# ncat.net
KiCad netlist of a schematic drawn in EAGLE
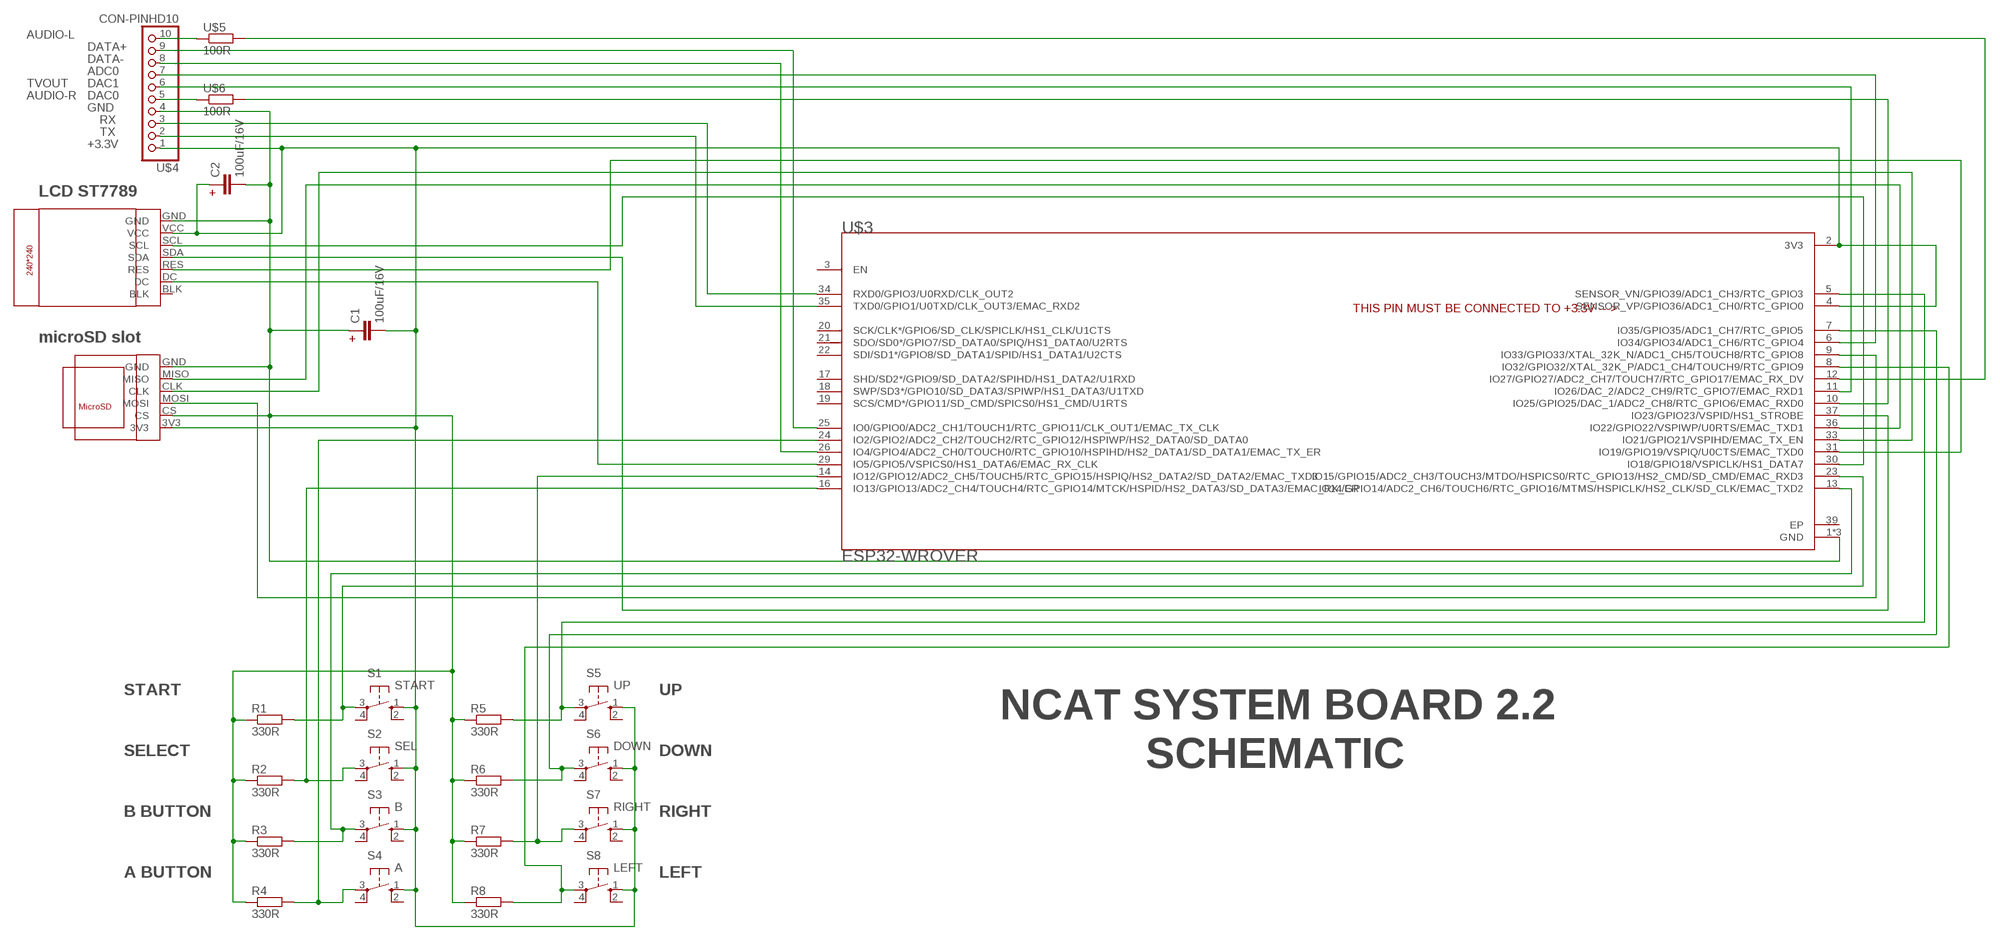
[diagram p0: schematic, sheet 1]

(export (version "E")
  (design (tool "Eeschema 10.0.6"))
  (components
    (comp (ref "C1")
      (value "100uF/16V")
      (footprint "eagle-import:C1210")
      (libsource (lib "eagle-import") (part "C-EUC1210"))
    )
    (comp (ref "C2")
      (value "100uF/16V")
      (footprint "eagle-import:C1210")
      (libsource (lib "eagle-import") (part "C-EUC1210"))
    )
    (comp (ref "R1")
      (value "330R")
      (footprint "eagle-import:R0204_5H")
      (libsource (lib "eagle-import") (part "RESISTORR204/5H"))
    )
    (comp (ref "R2")
      (value "330R")
      (footprint "eagle-import:R0204_5H")
      (libsource (lib "eagle-import") (part "RESISTORR204/5H"))
    )
    (comp (ref "R3")
      (value "330R")
      (footprint "eagle-import:R0204_5H")
      (libsource (lib "eagle-import") (part "RESISTORR204/5H"))
    )
    (comp (ref "R4")
      (value "330R")
      (footprint "eagle-import:R0204_5H")
      (libsource (lib "eagle-import") (part "RESISTORR204/5H"))
    )
    (comp (ref "R5")
      (value "330R")
      (footprint "eagle-import:R0204_5H")
      (libsource (lib "eagle-import") (part "RESISTORR204/5H"))
    )
    (comp (ref "R6")
      (value "330R")
      (footprint "eagle-import:R0204_5H")
      (libsource (lib "eagle-import") (part "RESISTORR204/5H"))
    )
    (comp (ref "R7")
      (value "330R")
      (footprint "eagle-import:R0204_5H")
      (libsource (lib "eagle-import") (part "RESISTORR204/5H"))
    )
    (comp (ref "R8")
      (value "330R")
      (footprint "eagle-import:R0204_5H")
      (libsource (lib "eagle-import") (part "RESISTORR204/5H"))
    )
    (comp (ref "S1")
      (value "START")
      (footprint "eagle-import:B3F-10XX")
      (fields (field (name "MPN") "B3F-1000"))
      (libsource (lib "eagle-import") (part "10-XX"))
    )
    (comp (ref "S2")
      (value "SEL")
      (footprint "eagle-import:B3F-10XX")
      (fields (field (name "MPN") "B3F-1000"))
      (libsource (lib "eagle-import") (part "10-XX"))
    )
    (comp (ref "S3")
      (value "B")
      (footprint "eagle-import:B3F-10XX")
      (fields (field (name "MPN") "B3F-1000"))
      (libsource (lib "eagle-import") (part "10-XX"))
    )
    (comp (ref "S4")
      (value "A")
      (footprint "eagle-import:B3F-10XX")
      (fields (field (name "MPN") "B3F-1000"))
      (libsource (lib "eagle-import") (part "10-XX"))
    )
    (comp (ref "S5")
      (value "UP")
      (footprint "eagle-import:B3F-10XX")
      (fields (field (name "MPN") "B3F-1000"))
      (libsource (lib "eagle-import") (part "10-XX"))
    )
    (comp (ref "S6")
      (value "DOWN")
      (footprint "eagle-import:B3F-10XX")
      (fields (field (name "MPN") "B3F-1000"))
      (libsource (lib "eagle-import") (part "10-XX"))
    )
    (comp (ref "S7")
      (value "RIGHT")
      (footprint "eagle-import:B3F-10XX")
      (fields (field (name "MPN") "B3F-1000"))
      (libsource (lib "eagle-import") (part "10-XX"))
    )
    (comp (ref "S8")
      (value "LEFT")
      (footprint "eagle-import:B3F-10XX")
      (fields (field (name "MPN") "B3F-1000"))
      (libsource (lib "eagle-import") (part "10-XX"))
    )
    (comp (ref "U$1")
      (value "MICROSD-CARD-MODULESMD")
      (footprint "eagle-import:MICROSD-CARD-MODULE-SMD")
      (libsource (lib "eagle-import") (part "MICROSD-CARD-MODULESMD"))
    )
    (comp (ref "U$3")
      (value "ESP32-WROVER")
      (footprint "eagle-import:XCVR-ESP32-WROVER")
      (libsource (lib "eagle-import") (part "ESP32-WROVER"))
    )
    (comp (ref "U$4")
      (value "CON-PINHD10")
      (footprint "eagle-import:PIN1X10")
      (libsource (lib "eagle-import") (part "CON-PINHD10"))
    )
    (comp (ref "U$5")
      (value "100R")
      (footprint "eagle-import:R1206_SMD")
      (libsource (lib "eagle-import") (part "RESISTORR1206/SMD"))
    )
    (comp (ref "U$6")
      (value "100R")
      (footprint "eagle-import:R1206_SMD")
      (libsource (lib "eagle-import") (part "RESISTORR1206/SMD"))
    )
    (comp (ref "U$7")
      (value "LCD-ST7789-1.3INCH")
      (footprint "eagle-import:LCD-ST7789-1.3INCH")
      (libsource (lib "eagle-import") (part "LCD-ST7789-1.3INCH"))
    )
  )
  (nets
    (net (code "1") (name "/EP") (class "Default")
      (node (ref "U$3") (pin "39") (pinfunction "EP_39") (pintype "power_in"))
    )
    (net (code "2") (name "Net-(C1-Pad1)") (class "Default")
      (node (ref "C1") (pin "1") (pinfunction "1_1") (pintype "passive"))
      (node (ref "C2") (pin "2") (pinfunction "2_2") (pintype "passive"))
      (node (ref "R1") (pin "1") (pinfunction "1_1") (pintype "passive"))
      (node (ref "R2") (pin "1") (pinfunction "1_1") (pintype "passive"))
      (node (ref "R3") (pin "1") (pinfunction "1_1") (pintype "passive"))
      (node (ref "R4") (pin "1") (pinfunction "1_1") (pintype "passive"))
      (node (ref "R5") (pin "1") (pinfunction "1_1") (pintype "passive"))
      (node (ref "R6") (pin "1") (pinfunction "1_1") (pintype "passive"))
      (node (ref "R7") (pin "1") (pinfunction "1_1") (pintype "passive"))
      (node (ref "R8") (pin "1") (pinfunction "1_1") (pintype "passive"))
      (node (ref "U$1") (pin "CS") (pinfunction "CS_CS") (pintype "bidirectional"))
      (node (ref "U$1") (pin "GND") (pinfunction "GND_GND") (pintype "bidirectional"))
      (node (ref "U$3") (pin "1") (pinfunction "GND_1") (pintype "power_in"))
      (node (ref "U$3") (pin "15") (pinfunction "GND_15") (pintype "power_in"))
      (node (ref "U$3") (pin "38") (pinfunction "GND_38") (pintype "power_in"))
      (node (ref "U$4") (pin "4") (pinfunction "4_4") (pintype "passive"))
      (node (ref "U$7") (pin "GND") (pinfunction "GND_GND") (pintype "bidirectional"))
    )
    (net (code "3") (name "Net-(S1-P)") (class "Default")
      (node (ref "R1") (pin "2") (pinfunction "2_2") (pintype "passive"))
      (node (ref "S1") (pin "3") (pinfunction "P_3") (pintype "passive"))
      (node (ref "U$3") (pin "23") (pinfunction "IO15/GPIO15/ADC2_CH3/TOUCH3/MTDO/HSPICS0/RTC_GPIO13/HS2_CMD/SD_CMD/EMAC_RXD3_23") (pintype "bidirectional"))
    )
    (net (code "4") (name "Net-(S1-S)") (class "Default")
      (node (ref "C1") (pin "2") (pinfunction "2_2") (pintype "passive"))
      (node (ref "C2") (pin "1") (pinfunction "1_1") (pintype "passive"))
      (node (ref "S1") (pin "1") (pinfunction "S_1") (pintype "passive"))
      (node (ref "S2") (pin "1") (pinfunction "S_1") (pintype "passive"))
      (node (ref "S3") (pin "1") (pinfunction "S_1") (pintype "passive"))
      (node (ref "S4") (pin "1") (pinfunction "S_1") (pintype "passive"))
      (node (ref "S5") (pin "1") (pinfunction "S_1") (pintype "passive"))
      (node (ref "S6") (pin "1") (pinfunction "S_1") (pintype "passive"))
      (node (ref "S7") (pin "1") (pinfunction "S_1") (pintype "passive"))
      (node (ref "S8") (pin "1") (pinfunction "S_1") (pintype "passive"))
      (node (ref "U$1") (pin "3V3") (pinfunction "3V3_3V3") (pintype "bidirectional"))
      (node (ref "U$3") (pin "2") (pinfunction "3V3_2") (pintype "power_in"))
      (node (ref "U$3") (pin "4") (pinfunction "SENSOR_VP/GPIO36/ADC1_CH0/RTC_GPIO0_4") (pintype "bidirectional"))
      (node (ref "U$4") (pin "1") (pinfunction "1_1") (pintype "passive"))
      (node (ref "U$7") (pin "VCC") (pinfunction "VCC_VCC") (pintype "bidirectional"))
    )
    (net (code "5") (name "Net-(S2-P)") (class "Default")
      (node (ref "R2") (pin "2") (pinfunction "2_2") (pintype "passive"))
      (node (ref "S2") (pin "3") (pinfunction "P_3") (pintype "passive"))
      (node (ref "U$3") (pin "16") (pinfunction "IO13/GPIO13/ADC2_CH4/TOUCH4/RTC_GPIO14/MTCK/HSPID/HS2_DATA3/SD_DATA3/EMAC_RX_ER_16") (pintype "bidirectional"))
    )
    (net (code "6") (name "Net-(S3-P)") (class "Default")
      (node (ref "R3") (pin "2") (pinfunction "2_2") (pintype "passive"))
      (node (ref "S3") (pin "3") (pinfunction "P_3") (pintype "passive"))
      (node (ref "U$3") (pin "13") (pinfunction "IO14/GPIO14/ADC2_CH6/TOUCH6/RTC_GPIO16/MTMS/HSPICLK/HS2_CLK/SD_CLK/EMAC_TXD2_13") (pintype "bidirectional"))
    )
    (net (code "7") (name "Net-(S4-P)") (class "Default")
      (node (ref "R4") (pin "2") (pinfunction "2_2") (pintype "passive"))
      (node (ref "S4") (pin "3") (pinfunction "P_3") (pintype "passive"))
      (node (ref "U$3") (pin "24") (pinfunction "IO2/GPIO2/ADC2_CH2/TOUCH2/RTC_GPIO12/HSPIWP/HS2_DATA0/SD_DATA0_24") (pintype "bidirectional"))
    )
    (net (code "8") (name "Net-(S5-P)") (class "Default")
      (node (ref "R5") (pin "2") (pinfunction "2_2") (pintype "passive"))
      (node (ref "S5") (pin "3") (pinfunction "P_3") (pintype "passive"))
      (node (ref "U$3") (pin "5") (pinfunction "SENSOR_VN/GPIO39/ADC1_CH3/RTC_GPIO3_5") (pintype "bidirectional"))
    )
    (net (code "9") (name "Net-(S6-P)") (class "Default")
      (node (ref "R6") (pin "2") (pinfunction "2_2") (pintype "passive"))
      (node (ref "S6") (pin "3") (pinfunction "P_3") (pintype "passive"))
      (node (ref "U$3") (pin "7") (pinfunction "IO35/GPIO35/ADC1_CH7/RTC_GPIO5_7") (pintype "bidirectional"))
    )
    (net (code "10") (name "Net-(S7-P)") (class "Default")
      (node (ref "R7") (pin "2") (pinfunction "2_2") (pintype "passive"))
      (node (ref "S7") (pin "3") (pinfunction "P_3") (pintype "passive"))
      (node (ref "U$3") (pin "14") (pinfunction "IO12/GPIO12/ADC2_CH5/TOUCH5/RTC_GPIO15/HSPIQ/HS2_DATA2/SD_DATA2/EMAC_TXD3_14") (pintype "bidirectional"))
    )
    (net (code "11") (name "Net-(S8-P)") (class "Default")
      (node (ref "R8") (pin "2") (pinfunction "2_2") (pintype "passive"))
      (node (ref "S8") (pin "3") (pinfunction "P_3") (pintype "passive"))
      (node (ref "U$3") (pin "8") (pinfunction "IO32/GPIO32/XTAL_32K_P/ADC1_CH4/TOUCH9/RTC_GPIO9_8") (pintype "bidirectional"))
    )
    (net (code "12") (name "Net-(U$3-IO0{slash}GPIO0{slash}ADC2_CH1{slash}TOUCH1{slash}RTC_GPIO11{slash}CLK_OUT1{slash}EMAC_TX_CLK)") (class "Default")
      (node (ref "U$3") (pin "25") (pinfunction "IO0/GPIO0/ADC2_CH1/TOUCH1/RTC_GPIO11/CLK_OUT1/EMAC_TX_CLK_25") (pintype "bidirectional"))
      (node (ref "U$4") (pin "9") (pinfunction "9_9") (pintype "passive"))
    )
    (net (code "13") (name "Net-(U$3-IO4{slash}GPIO4{slash}ADC2_CH0{slash}TOUCH0{slash}RTC_GPIO10{slash}HSPIHD{slash}HS2_DATA1{slash}SD_DATA1{slash}EMAC_TX_ER)") (class "Default")
      (node (ref "U$3") (pin "26") (pinfunction "IO4/GPIO4/ADC2_CH0/TOUCH0/RTC_GPIO10/HSPIHD/HS2_DATA1/SD_DATA1/EMAC_TX_ER_26") (pintype "bidirectional"))
      (node (ref "U$4") (pin "8") (pinfunction "8_8") (pintype "passive"))
    )
    (net (code "14") (name "Net-(U$3-IO5{slash}GPIO5{slash}VSPICS0{slash}HS1_DATA6{slash}EMAC_RX_CLK)") (class "Default")
      (node (ref "U$3") (pin "29") (pinfunction "IO5/GPIO5/VSPICS0/HS1_DATA6/EMAC_RX_CLK_29") (pintype "bidirectional"))
      (node (ref "U$7") (pin "DC") (pinfunction "DC_DC") (pintype "bidirectional"))
    )
    (net (code "15") (name "Net-(U$3-IO18{slash}GPIO18{slash}VSPICLK{slash}HS1_DATA7)") (class "Default")
      (node (ref "U$3") (pin "30") (pinfunction "IO18/GPIO18/VSPICLK/HS1_DATA7_30") (pintype "bidirectional"))
      (node (ref "U$7") (pin "SCL") (pinfunction "SCL_SCL") (pintype "bidirectional"))
    )
    (net (code "16") (name "Net-(U$3-IO19{slash}GPIO19{slash}VSPIQ{slash}U0CTS{slash}EMAC_TXD0)") (class "Default")
      (node (ref "U$3") (pin "31") (pinfunction "IO19/GPIO19/VSPIQ/U0CTS/EMAC_TXD0_31") (pintype "bidirectional"))
      (node (ref "U$7") (pin "RES") (pinfunction "RES_RES") (pintype "bidirectional"))
    )
    (net (code "17") (name "Net-(U$3-IO21{slash}GPIO21{slash}VSPIHD{slash}EMAC_TX_EN)") (class "Default")
      (node (ref "U$1") (pin "CLK") (pinfunction "CLK_CLK") (pintype "bidirectional"))
      (node (ref "U$3") (pin "33") (pinfunction "IO21/GPIO21/VSPIHD/EMAC_TX_EN_33") (pintype "bidirectional"))
    )
    (net (code "18") (name "Net-(U$3-IO22{slash}GPIO22{slash}VSPIWP{slash}U0RTS{slash}EMAC_TXD1)") (class "Default")
      (node (ref "U$1") (pin "MISO") (pinfunction "MISO_MISO") (pintype "bidirectional"))
      (node (ref "U$3") (pin "36") (pinfunction "IO22/GPIO22/VSPIWP/U0RTS/EMAC_TXD1_36") (pintype "bidirectional"))
    )
    (net (code "19") (name "Net-(U$3-IO23{slash}GPIO23{slash}VSPID{slash}HS1_STROBE)") (class "Default")
      (node (ref "U$3") (pin "37") (pinfunction "IO23/GPIO23/VSPID/HS1_STROBE_37") (pintype "bidirectional"))
      (node (ref "U$7") (pin "SDA") (pinfunction "SDA_SDA") (pintype "bidirectional"))
    )
    (net (code "20") (name "Net-(U$3-IO25{slash}GPIO25{slash}DAC_1{slash}ADC2_CH8{slash}RTC_GPIO6{slash}EMAC_RXD0)") (class "Default")
      (node (ref "U$3") (pin "10") (pinfunction "IO25/GPIO25/DAC_1/ADC2_CH8/RTC_GPIO6/EMAC_RXD0_10") (pintype "bidirectional"))
      (node (ref "U$6") (pin "2") (pinfunction "2_2") (pintype "passive"))
    )
    (net (code "21") (name "Net-(U$3-IO26{slash}DAC_2{slash}ADC2_CH9{slash}RTC_GPIO7{slash}EMAC_RXD1)") (class "Default")
      (node (ref "U$3") (pin "11") (pinfunction "IO26/DAC_2/ADC2_CH9/RTC_GPIO7/EMAC_RXD1_11") (pintype "bidirectional"))
      (node (ref "U$4") (pin "6") (pinfunction "6_6") (pintype "passive"))
    )
    (net (code "22") (name "Net-(U$3-IO27{slash}GPIO27{slash}ADC2_CH7{slash}TOUCH7{slash}RTC_GPIO17{slash}EMAC_RX_DV)") (class "Default")
      (node (ref "U$3") (pin "12") (pinfunction "IO27/GPIO27/ADC2_CH7/TOUCH7/RTC_GPIO17/EMAC_RX_DV_12") (pintype "bidirectional"))
      (node (ref "U$5") (pin "2") (pinfunction "2_2") (pintype "passive"))
    )
    (net (code "23") (name "Net-(U$3-IO33{slash}GPIO33{slash}XTAL_32K_N{slash}ADC1_CH5{slash}TOUCH8{slash}RTC_GPIO8)") (class "Default")
      (node (ref "U$1") (pin "MOSI") (pinfunction "MOSI_MOSI") (pintype "bidirectional"))
      (node (ref "U$3") (pin "9") (pinfunction "IO33/GPIO33/XTAL_32K_N/ADC1_CH5/TOUCH8/RTC_GPIO8_9") (pintype "bidirectional"))
    )
    (net (code "24") (name "Net-(U$3-IO34{slash}GPIO34{slash}ADC1_CH6{slash}RTC_GPIO4)") (class "Default")
      (node (ref "U$3") (pin "6") (pinfunction "IO34/GPIO34/ADC1_CH6/RTC_GPIO4_6") (pintype "bidirectional"))
      (node (ref "U$4") (pin "7") (pinfunction "7_7") (pintype "passive"))
    )
    (net (code "25") (name "Net-(U$3-RXD0{slash}GPIO3{slash}U0RXD{slash}CLK_OUT2)") (class "Default")
      (node (ref "U$3") (pin "34") (pinfunction "RXD0/GPIO3/U0RXD/CLK_OUT2_34") (pintype "bidirectional"))
      (node (ref "U$4") (pin "3") (pinfunction "3_3") (pintype "passive"))
    )
    (net (code "26") (name "Net-(U$3-TXD0{slash}GPIO1{slash}U0TXD{slash}CLK_OUT3{slash}EMAC_RXD2)") (class "Default")
      (node (ref "U$3") (pin "35") (pinfunction "TXD0/GPIO1/U0TXD/CLK_OUT3/EMAC_RXD2_35") (pintype "bidirectional"))
      (node (ref "U$4") (pin "2") (pinfunction "2_2") (pintype "passive"))
    )
    (net (code "27") (name "Net-(U$4-Pad5)") (class "Default")
      (node (ref "U$4") (pin "5") (pinfunction "5_5") (pintype "passive"))
      (node (ref "U$6") (pin "1") (pinfunction "1_1") (pintype "passive"))
    )
    (net (code "28") (name "Net-(U$4-Pad10)") (class "Default")
      (node (ref "U$4") (pin "10") (pinfunction "10_10") (pintype "passive"))
      (node (ref "U$5") (pin "1") (pinfunction "1_1") (pintype "passive"))
    )
    (net (code "29") (name "unconnected-(S1-P1-Pad4)") (class "Default")
      (node (ref "S1") (pin "4") (pinfunction "P1_4") (pintype "passive"))
    )
    (net (code "30") (name "unconnected-(S1-S1-Pad2)") (class "Default")
      (node (ref "S1") (pin "2") (pinfunction "S1_2") (pintype "passive"))
    )
    (net (code "31") (name "unconnected-(S2-P1-Pad4)") (class "Default")
      (node (ref "S2") (pin "4") (pinfunction "P1_4") (pintype "passive"))
    )
    (net (code "32") (name "unconnected-(S2-S1-Pad2)") (class "Default")
      (node (ref "S2") (pin "2") (pinfunction "S1_2") (pintype "passive"))
    )
    (net (code "33") (name "unconnected-(S3-P1-Pad4)") (class "Default")
      (node (ref "S3") (pin "4") (pinfunction "P1_4") (pintype "passive"))
    )
    (net (code "34") (name "unconnected-(S3-S1-Pad2)") (class "Default")
      (node (ref "S3") (pin "2") (pinfunction "S1_2") (pintype "passive"))
    )
    (net (code "35") (name "unconnected-(S4-P1-Pad4)") (class "Default")
      (node (ref "S4") (pin "4") (pinfunction "P1_4") (pintype "passive"))
    )
    (net (code "36") (name "unconnected-(S4-S1-Pad2)") (class "Default")
      (node (ref "S4") (pin "2") (pinfunction "S1_2") (pintype "passive"))
    )
    (net (code "37") (name "unconnected-(S5-P1-Pad4)") (class "Default")
      (node (ref "S5") (pin "4") (pinfunction "P1_4") (pintype "passive"))
    )
    (net (code "38") (name "unconnected-(S5-S1-Pad2)") (class "Default")
      (node (ref "S5") (pin "2") (pinfunction "S1_2") (pintype "passive"))
    )
    (net (code "39") (name "unconnected-(S6-P1-Pad4)") (class "Default")
      (node (ref "S6") (pin "4") (pinfunction "P1_4") (pintype "passive"))
    )
    (net (code "40") (name "unconnected-(S6-S1-Pad2)") (class "Default")
      (node (ref "S6") (pin "2") (pinfunction "S1_2") (pintype "passive"))
    )
    (net (code "41") (name "unconnected-(S7-P1-Pad4)") (class "Default")
      (node (ref "S7") (pin "4") (pinfunction "P1_4") (pintype "passive"))
    )
    (net (code "42") (name "unconnected-(S7-S1-Pad2)") (class "Default")
      (node (ref "S7") (pin "2") (pinfunction "S1_2") (pintype "passive"))
    )
    (net (code "43") (name "unconnected-(S8-P1-Pad4)") (class "Default")
      (node (ref "S8") (pin "4") (pinfunction "P1_4") (pintype "passive"))
    )
    (net (code "44") (name "unconnected-(S8-S1-Pad2)") (class "Default")
      (node (ref "S8") (pin "2") (pinfunction "S1_2") (pintype "passive"))
    )
    (net (code "45") (name "unconnected-(U$3-EN-Pad3)") (class "Default")
      (node (ref "U$3") (pin "3") (pinfunction "EN_3") (pintype "input"))
    )
    (net (code "46") (name "unconnected-(U$3-SCK{slash}CLK*{slash}GPIO6{slash}SD_CLK{slash}SPICLK{slash}HS1_CLK{slash}U1CTS-Pad20)") (class "Default")
      (node (ref "U$3") (pin "20") (pinfunction "SCK/CLK*/GPIO6/SD_CLK/SPICLK/HS1_CLK/U1CTS_20") (pintype "bidirectional"))
    )
    (net (code "47") (name "unconnected-(U$3-SCS{slash}CMD*{slash}GPIO11{slash}SD_CMD{slash}SPICS0{slash}HS1_CMD{slash}U1RTS-Pad19)") (class "Default")
      (node (ref "U$3") (pin "19") (pinfunction "SCS/CMD*/GPIO11/SD_CMD/SPICS0/HS1_CMD/U1RTS_19") (pintype "bidirectional"))
    )
    (net (code "48") (name "unconnected-(U$3-SDI{slash}SD1*{slash}GPIO8{slash}SD_DATA1{slash}SPID{slash}HS1_DATA1{slash}U2CTS-Pad22)") (class "Default")
      (node (ref "U$3") (pin "22") (pinfunction "SDI/SD1*/GPIO8/SD_DATA1/SPID/HS1_DATA1/U2CTS_22") (pintype "bidirectional"))
    )
    (net (code "49") (name "unconnected-(U$3-SDO{slash}SD0*{slash}GPIO7{slash}SD_DATA0{slash}SPIQ{slash}HS1_DATA0{slash}U2RTS-Pad21)") (class "Default")
      (node (ref "U$3") (pin "21") (pinfunction "SDO/SD0*/GPIO7/SD_DATA0/SPIQ/HS1_DATA0/U2RTS_21") (pintype "bidirectional"))
    )
    (net (code "50") (name "unconnected-(U$3-SHD{slash}SD2*{slash}GPIO9{slash}SD_DATA2{slash}SPIHD{slash}HS1_DATA2{slash}U1RXD-Pad17)") (class "Default")
      (node (ref "U$3") (pin "17") (pinfunction "SHD/SD2*/GPIO9/SD_DATA2/SPIHD/HS1_DATA2/U1RXD_17") (pintype "bidirectional"))
    )
    (net (code "51") (name "unconnected-(U$3-SWP{slash}SD3*{slash}GPIO10{slash}SD_DATA3{slash}SPIWP{slash}HS1_DATA3{slash}U1TXD-Pad18)") (class "Default")
      (node (ref "U$3") (pin "18") (pinfunction "SWP/SD3*/GPIO10/SD_DATA3/SPIWP/HS1_DATA3/U1TXD_18") (pintype "bidirectional"))
    )
    (net (code "52") (name "unconnected-(U$7-PadBLK)") (class "Default")
      (node (ref "U$7") (pin "BLK") (pinfunction "BLK_BLK") (pintype "bidirectional"))
    )
  )
)
